# Peripherals.net
KiCad netlist of a schematic drawn in Altium Designer
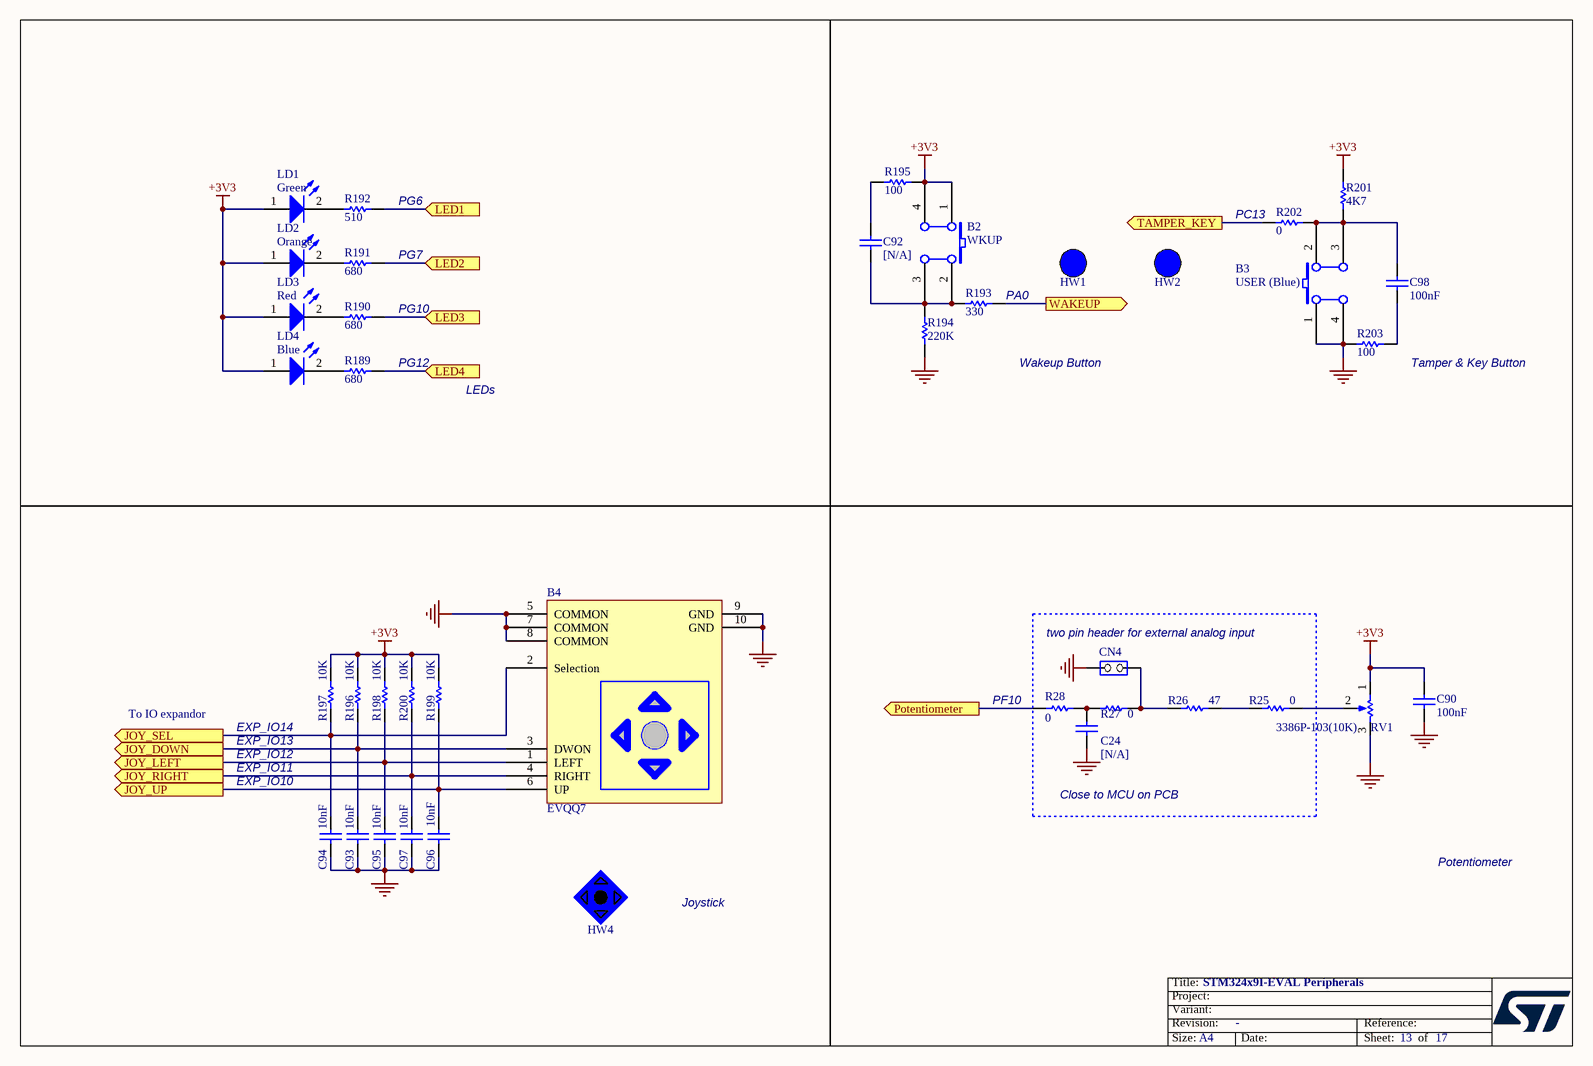
[diagram p0: Peripherals.SchDoc]

(export (version "E")
  (design (tool "Eeschema 10.0.6"))
  (components
    (comp (ref "B2")
      (value "WKUP")
      (footprint "PB10")
      (description "SE PUSHBUTTON")
      (libsource (lib "Documents") (part "SW PUSHBUTTON"))
    )
    (comp (ref "B3")
      (value "USER (Blue)")
      (footprint "PB10")
      (description "SE PUSHBUTTON")
      (libsource (lib "Documents") (part "SW PUSHBUTTON"))
    )
    (comp (ref "B4") (value "EVQQ7") (footprint "SW-JOY") (libsource (lib "mb1045") (part "EVQQ7")))
    (comp (ref "C24")
      (value "[N/A]")
      (footprint "0603C")
      (description "Capacitor")
      (fields (field (name "PUBLISHER") "Altium Limited"))
      (libsource (lib "Miscellaneous Devices") (part "cap"))
    )
    (comp (ref "C90")
      (value "100nF")
      (footprint "0603C")
      (description "Capacitor")
      (fields (field (name "PUBLISHER") "Altium Limited"))
      (libsource (lib "Miscellaneous Devices") (part "CAP"))
    )
    (comp (ref "C92")
      (value "[N/A]")
      (footprint "0603C")
      (description "Capacitor")
      (fields (field (name "PUBLISHER") "Altium Limited"))
      (libsource (lib "Miscellaneous Devices") (part "CAP"))
    )
    (comp (ref "C93")
      (value "10nF")
      (footprint "0603C")
      (description "Capacitor")
      (fields (field (name "PUBLISHER") "Altium Limited"))
      (libsource (lib "Miscellaneous Devices") (part "CAP"))
    )
    (comp (ref "C94")
      (value "10nF")
      (footprint "0603C")
      (description "Capacitor")
      (fields (field (name "PUBLISHER") "Altium Limited"))
      (libsource (lib "Miscellaneous Devices") (part "CAP"))
    )
    (comp (ref "C95")
      (value "10nF")
      (footprint "0603C")
      (description "Capacitor")
      (fields (field (name "PUBLISHER") "Altium Limited"))
      (libsource (lib "Miscellaneous Devices") (part "CAP"))
    )
    (comp (ref "C96")
      (value "10nF")
      (footprint "0603C")
      (description "Capacitor")
      (fields (field (name "PUBLISHER") "Altium Limited"))
      (libsource (lib "Miscellaneous Devices") (part "CAP"))
    )
    (comp (ref "C97")
      (value "10nF")
      (footprint "0603C")
      (description "Capacitor")
      (fields (field (name "PUBLISHER") "Altium Limited"))
      (libsource (lib "Miscellaneous Devices") (part "CAP"))
    )
    (comp (ref "C98")
      (value "100nF")
      (footprint "0603C")
      (description "Capacitor")
      (fields (field (name "PUBLISHER") "Altium Limited"))
      (libsource (lib "Miscellaneous Devices") (part "CAP"))
    )
    (comp (ref "CN4") (value "~") (footprint "SIP2") (libsource (lib "*") (part "JP2")))
    (comp (ref "HW1") (value "BUTTON_HAT_BLUE") (libsource (lib "mb1045") (part "BUTTON_HAT_BLUE")))
    (comp (ref "HW2") (value "BUTTON_HAT_BLUE") (libsource (lib "mb1045") (part "BUTTON_HAT_BLUE")))
    (comp (ref "HW4") (value "JOYSTICK_BLUE_HAT") (libsource (lib "mb1045") (part "JOYSTICK_BLUE_HAT")))
    (comp (ref "LD1")
      (value "Green")
      (footprint "0603D")
      (description "Typical RED, GREEN, YELLOW, AMBER GaAs LED")
      (fields (field (name "PUBLISHER") "Altium Limited"))
      (libsource (lib "Miscellaneous Devices") (part "LED2"))
    )
    (comp (ref "LD2")
      (value "Orange")
      (footprint "0603D")
      (description "Typical RED, GREEN, YELLOW, AMBER GaAs LED")
      (fields (field (name "PUBLISHER") "Altium Limited"))
      (libsource (lib "Miscellaneous Devices") (part "LED2"))
    )
    (comp (ref "LD3")
      (value "Red")
      (footprint "0603D")
      (description "Typical RED, GREEN, YELLOW, AMBER GaAs LED")
      (fields (field (name "PUBLISHER") "Altium Limited"))
      (libsource (lib "Miscellaneous Devices") (part "LED2"))
    )
    (comp (ref "LD4")
      (value "Blue")
      (footprint "0603D")
      (description "Typical RED, GREEN, YELLOW, AMBER GaAs LED")
      (fields (field (name "PUBLISHER") "Altium Limited"))
      (libsource (lib "Miscellaneous Devices") (part "LED2"))
    )
    (comp (ref "R25")
      (value "0")
      (footprint "0603R")
      (description "Resistor")
      (fields (field (name "PUBLISHER") "Altium Limited"))
      (libsource (lib "Miscellaneous Devices") (part "Res1"))
    )
    (comp (ref "R26")
      (value "47")
      (footprint "0603R")
      (description "Resistor")
      (fields (field (name "PUBLISHER") "Altium Limited"))
      (libsource (lib "Miscellaneous Devices") (part "Res1"))
    )
    (comp (ref "R27")
      (value "0")
      (footprint "0603R")
      (description "Resistor")
      (fields (field (name "PUBLISHER") "Altium Limited"))
      (libsource (lib "Miscellaneous Devices") (part "Res1"))
    )
    (comp (ref "R28")
      (value "0")
      (footprint "0603R")
      (description "Resistor")
      (fields (field (name "PUBLISHER") "Altium Limited"))
      (libsource (lib "Miscellaneous Devices") (part "Res1"))
    )
    (comp (ref "R189")
      (value "680")
      (footprint "0603R")
      (description "Resistor")
      (fields (field (name "PUBLISHER") "Altium Limited"))
      (libsource (lib "Miscellaneous Devices") (part "Res1"))
    )
    (comp (ref "R190")
      (value "680")
      (footprint "0603R")
      (description "Resistor")
      (fields (field (name "PUBLISHER") "Altium Limited"))
      (libsource (lib "Miscellaneous Devices") (part "Res1"))
    )
    (comp (ref "R191")
      (value "680")
      (footprint "0603R")
      (description "Resistor")
      (fields (field (name "PUBLISHER") "Altium Limited"))
      (libsource (lib "Miscellaneous Devices") (part "Res1"))
    )
    (comp (ref "R192")
      (value "510")
      (footprint "0603R")
      (description "Resistor")
      (fields (field (name "PUBLISHER") "Altium Limited"))
      (libsource (lib "Miscellaneous Devices") (part "Res1"))
    )
    (comp (ref "R193")
      (value "330")
      (footprint "0603R")
      (description "Resistor")
      (fields (field (name "PUBLISHER") "Altium Limited"))
      (libsource (lib "Miscellaneous Devices") (part "Res1"))
    )
    (comp (ref "R194")
      (value "220K")
      (footprint "0603R")
      (description "Resistor")
      (fields (field (name "PUBLISHER") "Altium Limited"))
      (libsource (lib "Miscellaneous Devices") (part "res1"))
    )
    (comp (ref "R195")
      (value "100")
      (footprint "0603R")
      (description "Resistor")
      (fields (field (name "PUBLISHER") "Altium Limited"))
      (libsource (lib "Miscellaneous Devices") (part "Res1"))
    )
    (comp (ref "R196")
      (value "10K")
      (footprint "0603R")
      (description "Resistor")
      (fields (field (name "PUBLISHER") "Altium Limited"))
      (libsource (lib "Miscellaneous Devices") (part "res1"))
    )
    (comp (ref "R197")
      (value "10K")
      (footprint "0603R")
      (description "Resistor")
      (fields (field (name "PUBLISHER") "Altium Limited"))
      (libsource (lib "Miscellaneous Devices") (part "res1"))
    )
    (comp (ref "R198")
      (value "10K")
      (footprint "0603R")
      (description "Resistor")
      (fields (field (name "PUBLISHER") "Altium Limited"))
      (libsource (lib "Miscellaneous Devices") (part "res1"))
    )
    (comp (ref "R199")
      (value "10K")
      (footprint "0603R")
      (description "Resistor")
      (fields (field (name "PUBLISHER") "Altium Limited"))
      (libsource (lib "Miscellaneous Devices") (part "res1"))
    )
    (comp (ref "R200")
      (value "10K")
      (footprint "0603R")
      (description "Resistor")
      (fields (field (name "PUBLISHER") "Altium Limited"))
      (libsource (lib "Miscellaneous Devices") (part "res1"))
    )
    (comp (ref "R201")
      (value "4K7")
      (footprint "0603R")
      (description "Resistor")
      (fields (field (name "PUBLISHER") "Altium Limited"))
      (libsource (lib "Miscellaneous Devices") (part "res1"))
    )
    (comp (ref "R202")
      (value "0")
      (footprint "0603R")
      (description "Resistor")
      (fields (field (name "PUBLISHER") "Altium Limited"))
      (libsource (lib "Miscellaneous Devices") (part "Res1"))
    )
    (comp (ref "R203")
      (value "100")
      (footprint "0603R")
      (description "Resistor")
      (fields (field (name "PUBLISHER") "Altium Limited"))
      (libsource (lib "Miscellaneous Devices") (part "Res1"))
    )
    (comp (ref "RV1")
      (value "3386P-103(10K)")
      (footprint "3386P")
      (libsource (lib "STR910_SCHLIB") (part "RV"))
    )
  )
  (nets
    (net (code "1") (name "+3V3") (class "Default")
      (node (ref "B2") (pin "1") (pinfunction "A0_1") (pintype "passive"))
      (node (ref "B2") (pin "4") (pinfunction "A1_4") (pintype "passive"))
      (node (ref "C90") (pin "1") (pinfunction "1_1") (pintype "passive"))
      (node (ref "LD1") (pin "1") (pinfunction "A_1") (pintype "passive"))
      (node (ref "LD2") (pin "1") (pinfunction "A_1") (pintype "passive"))
      (node (ref "LD3") (pin "1") (pinfunction "A_1") (pintype "passive"))
      (node (ref "LD4") (pin "1") (pinfunction "A_1") (pintype "passive"))
      (node (ref "R195") (pin "1") (pinfunction "1_1") (pintype "passive"))
      (node (ref "R196") (pin "1") (pinfunction "1_1") (pintype "passive"))
      (node (ref "R197") (pin "1") (pinfunction "1_1") (pintype "passive"))
      (node (ref "R198") (pin "1") (pinfunction "1_1") (pintype "passive"))
      (node (ref "R199") (pin "1") (pinfunction "1_1") (pintype "passive"))
      (node (ref "R200") (pin "1") (pinfunction "1_1") (pintype "passive"))
      (node (ref "R201") (pin "2") (pinfunction "2_2") (pintype "passive"))
      (node (ref "RV1") (pin "1") (pinfunction "BOT_1") (pintype "passive"))
    )
    (net (code "2") (name "/JOY_DOWN") (class "Default")
      (node (ref "B4") (pin "3") (pinfunction "DWON_3") (pintype "passive"))
      (node (ref "C93") (pin "2") (pinfunction "2_2") (pintype "passive"))
      (node (ref "R196") (pin "2") (pinfunction "2_2") (pintype "passive"))
    )
    (net (code "3") (name "/JOY_LEFT") (class "Default")
      (node (ref "B4") (pin "1") (pinfunction "LEFT_1") (pintype "passive"))
      (node (ref "C95") (pin "2") (pinfunction "2_2") (pintype "passive"))
      (node (ref "R198") (pin "2") (pinfunction "2_2") (pintype "passive"))
    )
    (net (code "4") (name "/JOY_RIGHT") (class "Default")
      (node (ref "B4") (pin "4") (pinfunction "RIGHT_4") (pintype "passive"))
      (node (ref "C97") (pin "2") (pinfunction "2_2") (pintype "passive"))
      (node (ref "R200") (pin "2") (pinfunction "2_2") (pintype "passive"))
    )
    (net (code "5") (name "/JOY_SEL") (class "Default")
      (node (ref "B4") (pin "2") (pinfunction "Selection_2") (pintype "passive"))
      (node (ref "C94") (pin "2") (pinfunction "2_2") (pintype "passive"))
      (node (ref "R197") (pin "2") (pinfunction "2_2") (pintype "passive"))
    )
    (net (code "6") (name "/JOY_UP") (class "Default")
      (node (ref "B4") (pin "6") (pinfunction "UP_6") (pintype "passive"))
      (node (ref "C96") (pin "2") (pinfunction "2_2") (pintype "passive"))
      (node (ref "R199") (pin "2") (pinfunction "2_2") (pintype "passive"))
    )
    (net (code "7") (name "/LED1") (class "Default")
      (node (ref "R192") (pin "1") (pinfunction "1_1") (pintype "passive"))
    )
    (net (code "8") (name "/LED2") (class "Default")
      (node (ref "R191") (pin "1") (pinfunction "1_1") (pintype "passive"))
    )
    (net (code "9") (name "/LED3") (class "Default")
      (node (ref "R190") (pin "1") (pinfunction "1_1") (pintype "passive"))
    )
    (net (code "10") (name "/LED4") (class "Default")
      (node (ref "R189") (pin "1") (pinfunction "1_1") (pintype "passive"))
    )
    (net (code "11") (name "/Potentiometer") (class "Default")
      (node (ref "R28") (pin "2") (pinfunction "2_2") (pintype "passive"))
    )
    (net (code "12") (name "/TAMPER_KEY") (class "Default")
      (node (ref "R202") (pin "2") (pinfunction "2_2") (pintype "passive"))
    )
    (net (code "13") (name "/WAKEUP") (class "Default")
      (node (ref "R193") (pin "2") (pinfunction "2_2") (pintype "passive"))
    )
    (net (code "14") (name "GND") (class "Default")
      (node (ref "B3") (pin "1") (pinfunction "A0_1") (pintype "passive"))
      (node (ref "B3") (pin "4") (pinfunction "A1_4") (pintype "passive"))
      (node (ref "B4") (pin "10") (pinfunction "GND_10") (pintype "passive"))
      (node (ref "B4") (pin "5") (pinfunction "COMMON_5") (pintype "passive"))
      (node (ref "B4") (pin "7") (pinfunction "COMMON_7") (pintype "passive"))
      (node (ref "B4") (pin "8") (pinfunction "COMMON_8") (pintype "passive"))
      (node (ref "B4") (pin "9") (pinfunction "GND_9") (pintype "passive"))
      (node (ref "C24") (pin "1") (pinfunction "1_1") (pintype "passive"))
      (node (ref "C90") (pin "2") (pinfunction "2_2") (pintype "passive"))
      (node (ref "C93") (pin "1") (pinfunction "1_1") (pintype "passive"))
      (node (ref "C94") (pin "1") (pinfunction "1_1") (pintype "passive"))
      (node (ref "C95") (pin "1") (pinfunction "1_1") (pintype "passive"))
      (node (ref "C96") (pin "1") (pinfunction "1_1") (pintype "passive"))
      (node (ref "C97") (pin "1") (pinfunction "1_1") (pintype "passive"))
      (node (ref "CN4") (pin "2") (pinfunction "NO_2") (pintype "passive"))
      (node (ref "R194") (pin "2") (pinfunction "2_2") (pintype "passive"))
      (node (ref "R203") (pin "1") (pinfunction "1_1") (pintype "passive"))
      (node (ref "RV1") (pin "3") (pinfunction "TOP_3") (pintype "passive"))
    )
    (net (code "15") (name "Net-(B2-B0)") (class "Default")
      (node (ref "B2") (pin "2") (pinfunction "B0_2") (pintype "passive"))
      (node (ref "B2") (pin "3") (pinfunction "B1_3") (pintype "passive"))
      (node (ref "C92") (pin "2") (pinfunction "2_2") (pintype "passive"))
      (node (ref "R193") (pin "1") (pinfunction "1_1") (pintype "passive"))
      (node (ref "R194") (pin "1") (pinfunction "1_1") (pintype "passive"))
    )
    (net (code "16") (name "Net-(B3-B0)") (class "Default")
      (node (ref "B3") (pin "2") (pinfunction "B0_2") (pintype "passive"))
      (node (ref "B3") (pin "3") (pinfunction "B1_3") (pintype "passive"))
      (node (ref "C98") (pin "2") (pinfunction "2_2") (pintype "passive"))
      (node (ref "R201") (pin "1") (pinfunction "1_1") (pintype "passive"))
      (node (ref "R202") (pin "1") (pinfunction "1_1") (pintype "passive"))
    )
    (net (code "17") (name "Net-(C24-Pad2)") (class "Default")
      (node (ref "C24") (pin "2") (pinfunction "2_2") (pintype "passive"))
      (node (ref "R27") (pin "1") (pinfunction "1_1") (pintype "passive"))
      (node (ref "R28") (pin "1") (pinfunction "1_1") (pintype "passive"))
    )
    (net (code "18") (name "Net-(C92-Pad1)") (class "Default")
      (node (ref "C92") (pin "1") (pinfunction "1_1") (pintype "passive"))
      (node (ref "R195") (pin "2") (pinfunction "2_2") (pintype "passive"))
    )
    (net (code "19") (name "Net-(C98-Pad1)") (class "Default")
      (node (ref "C98") (pin "1") (pinfunction "1_1") (pintype "passive"))
      (node (ref "R203") (pin "2") (pinfunction "2_2") (pintype "passive"))
    )
    (net (code "20") (name "Net-(CN4-COMMON)") (class "Default")
      (node (ref "CN4") (pin "1") (pinfunction "COMMON_1") (pintype "passive"))
      (node (ref "R26") (pin "1") (pinfunction "1_1") (pintype "passive"))
      (node (ref "R27") (pin "2") (pinfunction "2_2") (pintype "passive"))
    )
    (net (code "21") (name "Net-(LD1-K)") (class "Default")
      (node (ref "LD1") (pin "2") (pinfunction "K_2") (pintype "passive"))
      (node (ref "R192") (pin "2") (pinfunction "2_2") (pintype "passive"))
    )
    (net (code "22") (name "Net-(LD2-K)") (class "Default")
      (node (ref "LD2") (pin "2") (pinfunction "K_2") (pintype "passive"))
      (node (ref "R191") (pin "2") (pinfunction "2_2") (pintype "passive"))
    )
    (net (code "23") (name "Net-(LD3-K)") (class "Default")
      (node (ref "LD3") (pin "2") (pinfunction "K_2") (pintype "passive"))
      (node (ref "R190") (pin "2") (pinfunction "2_2") (pintype "passive"))
    )
    (net (code "24") (name "Net-(LD4-K)") (class "Default")
      (node (ref "LD4") (pin "2") (pinfunction "K_2") (pintype "passive"))
      (node (ref "R189") (pin "2") (pinfunction "2_2") (pintype "passive"))
    )
    (net (code "25") (name "Net-(R25-Pad1)") (class "Default")
      (node (ref "R25") (pin "1") (pinfunction "1_1") (pintype "passive"))
      (node (ref "R26") (pin "2") (pinfunction "2_2") (pintype "passive"))
    )
    (net (code "26") (name "Net-(RV1-TAP)") (class "Default")
      (node (ref "R25") (pin "2") (pinfunction "2_2") (pintype "passive"))
      (node (ref "RV1") (pin "2") (pinfunction "TAP_2") (pintype "passive"))
    )
  )
)
